# Sheet1.net
KiCad netlist of a schematic drawn in Altium Designer
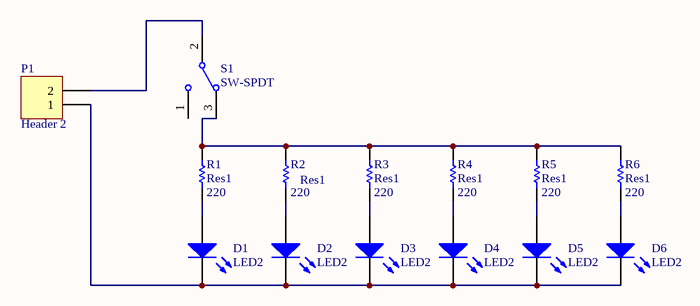
[diagram p0: Sheet1.SchDoc]

(export (version "E")
  (design (tool "Eeschema 10.0.6"))
  (components
    (comp (ref "D1")
      (value "LED2")
      (footprint "AXIAL-0.3")
      (description "Typical RED, GREEN, YELLOW, AMBER GaAs LED")
      (fields (field (name "PUBLISHER") "Altium Limited"))
      (libsource (lib "Miscellaneous Devices") (part "LED2"))
    )
    (comp (ref "D2")
      (value "LED2")
      (footprint "AXIAL-0.3")
      (description "Typical RED, GREEN, YELLOW, AMBER GaAs LED")
      (fields (field (name "PUBLISHER") "Altium Limited"))
      (libsource (lib "Miscellaneous Devices") (part "LED2"))
    )
    (comp (ref "D3")
      (value "LED2")
      (footprint "AXIAL-0.3")
      (description "Typical RED, GREEN, YELLOW, AMBER GaAs LED")
      (fields (field (name "PUBLISHER") "Altium Limited"))
      (libsource (lib "Miscellaneous Devices") (part "LED2"))
    )
    (comp (ref "D4")
      (value "LED2")
      (footprint "AXIAL-0.3")
      (description "Typical RED, GREEN, YELLOW, AMBER GaAs LED")
      (fields (field (name "PUBLISHER") "Altium Limited"))
      (libsource (lib "Miscellaneous Devices") (part "LED2"))
    )
    (comp (ref "D5")
      (value "LED2")
      (footprint "AXIAL-0.3")
      (description "Typical RED, GREEN, YELLOW, AMBER GaAs LED")
      (fields (field (name "PUBLISHER") "Altium Limited"))
      (libsource (lib "Miscellaneous Devices") (part "LED2"))
    )
    (comp (ref "D6")
      (value "LED2")
      (footprint "AXIAL-0.3")
      (description "Typical RED, GREEN, YELLOW, AMBER GaAs LED")
      (fields (field (name "PUBLISHER") "Altium Limited"))
      (libsource (lib "Miscellaneous Devices") (part "LED2"))
    )
    (comp (ref "P1")
      (value "Header 2")
      (footprint "HDR1X2")
      (description "Header, 2-Pin")
      (fields (field (name "PUBLISHER") "Altium Limited"))
      (libsource (lib "Miscellaneous Connectors") (part "Header 2"))
    )
    (comp (ref "R1")
      (value "Res1")
      (footprint "AXIAL-0.3")
      (description "Resistor")
      (fields (field (name "ALTIUM_VALUE") "220") (field (name "PUBLISHER") "Altium Limited"))
      (libsource (lib "Miscellaneous Devices") (part "Res1"))
    )
    (comp (ref "R2")
      (value "Res1")
      (footprint "AXIAL-0.3")
      (description "Resistor")
      (fields (field (name "ALTIUM_VALUE") "220") (field (name "PUBLISHER") "Altium Limited"))
      (libsource (lib "Miscellaneous Devices") (part "Res1"))
    )
    (comp (ref "R3")
      (value "Res1")
      (footprint "AXIAL-0.3")
      (description "Resistor")
      (fields (field (name "ALTIUM_VALUE") "220") (field (name "PUBLISHER") "Altium Limited"))
      (libsource (lib "Miscellaneous Devices") (part "Res1"))
    )
    (comp (ref "R4")
      (value "Res1")
      (footprint "AXIAL-0.3")
      (description "Resistor")
      (fields (field (name "ALTIUM_VALUE") "220") (field (name "PUBLISHER") "Altium Limited"))
      (libsource (lib "Miscellaneous Devices") (part "Res1"))
    )
    (comp (ref "R5")
      (value "Res1")
      (footprint "AXIAL-0.3")
      (description "Resistor")
      (fields (field (name "ALTIUM_VALUE") "220") (field (name "PUBLISHER") "Altium Limited"))
      (libsource (lib "Miscellaneous Devices") (part "Res1"))
    )
    (comp (ref "R6")
      (value "Res1")
      (footprint "AXIAL-0.3")
      (description "Resistor")
      (fields (field (name "ALTIUM_VALUE") "220") (field (name "PUBLISHER") "Altium Limited"))
      (libsource (lib "Miscellaneous Devices") (part "Res1"))
    )
    (comp (ref "S1")
      (value "SW-SPDT")
      (footprint "TL36WW15050")
      (description "SPDT Subminiature Toggle Switch, Right Angle Mounting, Vertical Actuation")
      (fields (field (name "PUBLISHER") "Altium Limited"))
      (libsource (lib "Miscellaneous Devices") (part "SW-SPDT"))
    )
  )
  (nets
    (net (code "1") (name "Net-(D1-A)") (class "Default")
      (node (ref "D1") (pin "1") (pinfunction "A_1") (pintype "passive"))
      (node (ref "R1") (pin "1") (pinfunction "1_1") (pintype "passive"))
    )
    (net (code "2") (name "Net-(D1-K)") (class "Default")
      (node (ref "D1") (pin "2") (pinfunction "K_2") (pintype "passive"))
      (node (ref "D2") (pin "2") (pinfunction "K_2") (pintype "passive"))
      (node (ref "D3") (pin "2") (pinfunction "K_2") (pintype "passive"))
      (node (ref "D4") (pin "2") (pinfunction "K_2") (pintype "passive"))
      (node (ref "D5") (pin "2") (pinfunction "K_2") (pintype "passive"))
      (node (ref "D6") (pin "2") (pinfunction "K_2") (pintype "passive"))
      (node (ref "P1") (pin "1") (pinfunction "1_1") (pintype "passive"))
    )
    (net (code "3") (name "Net-(D2-A)") (class "Default")
      (node (ref "D2") (pin "1") (pinfunction "A_1") (pintype "passive"))
      (node (ref "R2") (pin "1") (pinfunction "1_1") (pintype "passive"))
    )
    (net (code "4") (name "Net-(D3-A)") (class "Default")
      (node (ref "D3") (pin "1") (pinfunction "A_1") (pintype "passive"))
      (node (ref "R3") (pin "1") (pinfunction "1_1") (pintype "passive"))
    )
    (net (code "5") (name "Net-(D4-A)") (class "Default")
      (node (ref "D4") (pin "1") (pinfunction "A_1") (pintype "passive"))
      (node (ref "R4") (pin "1") (pinfunction "1_1") (pintype "passive"))
    )
    (net (code "6") (name "Net-(D5-A)") (class "Default")
      (node (ref "D5") (pin "1") (pinfunction "A_1") (pintype "passive"))
      (node (ref "R5") (pin "1") (pinfunction "1_1") (pintype "passive"))
    )
    (net (code "7") (name "Net-(D6-A)") (class "Default")
      (node (ref "D6") (pin "1") (pinfunction "A_1") (pintype "passive"))
      (node (ref "R6") (pin "1") (pinfunction "1_1") (pintype "passive"))
    )
    (net (code "8") (name "Net-(P1-Pad2)") (class "Default")
      (node (ref "P1") (pin "2") (pinfunction "2_2") (pintype "passive"))
      (node (ref "S1") (pin "2") (pinfunction "2_2") (pintype "passive"))
    )
    (net (code "9") (name "Net-(R1-Pad2)") (class "Default")
      (node (ref "R1") (pin "2") (pinfunction "2_2") (pintype "passive"))
      (node (ref "R2") (pin "2") (pinfunction "2_2") (pintype "passive"))
      (node (ref "R3") (pin "2") (pinfunction "2_2") (pintype "passive"))
      (node (ref "R4") (pin "2") (pinfunction "2_2") (pintype "passive"))
      (node (ref "R5") (pin "2") (pinfunction "2_2") (pintype "passive"))
      (node (ref "R6") (pin "2") (pinfunction "2_2") (pintype "passive"))
      (node (ref "S1") (pin "3") (pinfunction "3_3") (pintype "passive"))
    )
    (net (code "10") (name "unconnected-(S1-Pad1)") (class "Default")
      (node (ref "S1") (pin "1") (pinfunction "1_1") (pintype "passive"))
    )
  )
)
